# SUperUnioc_analog_ServosExtension.net
KiCad netlist of a schematic drawn in EAGLE
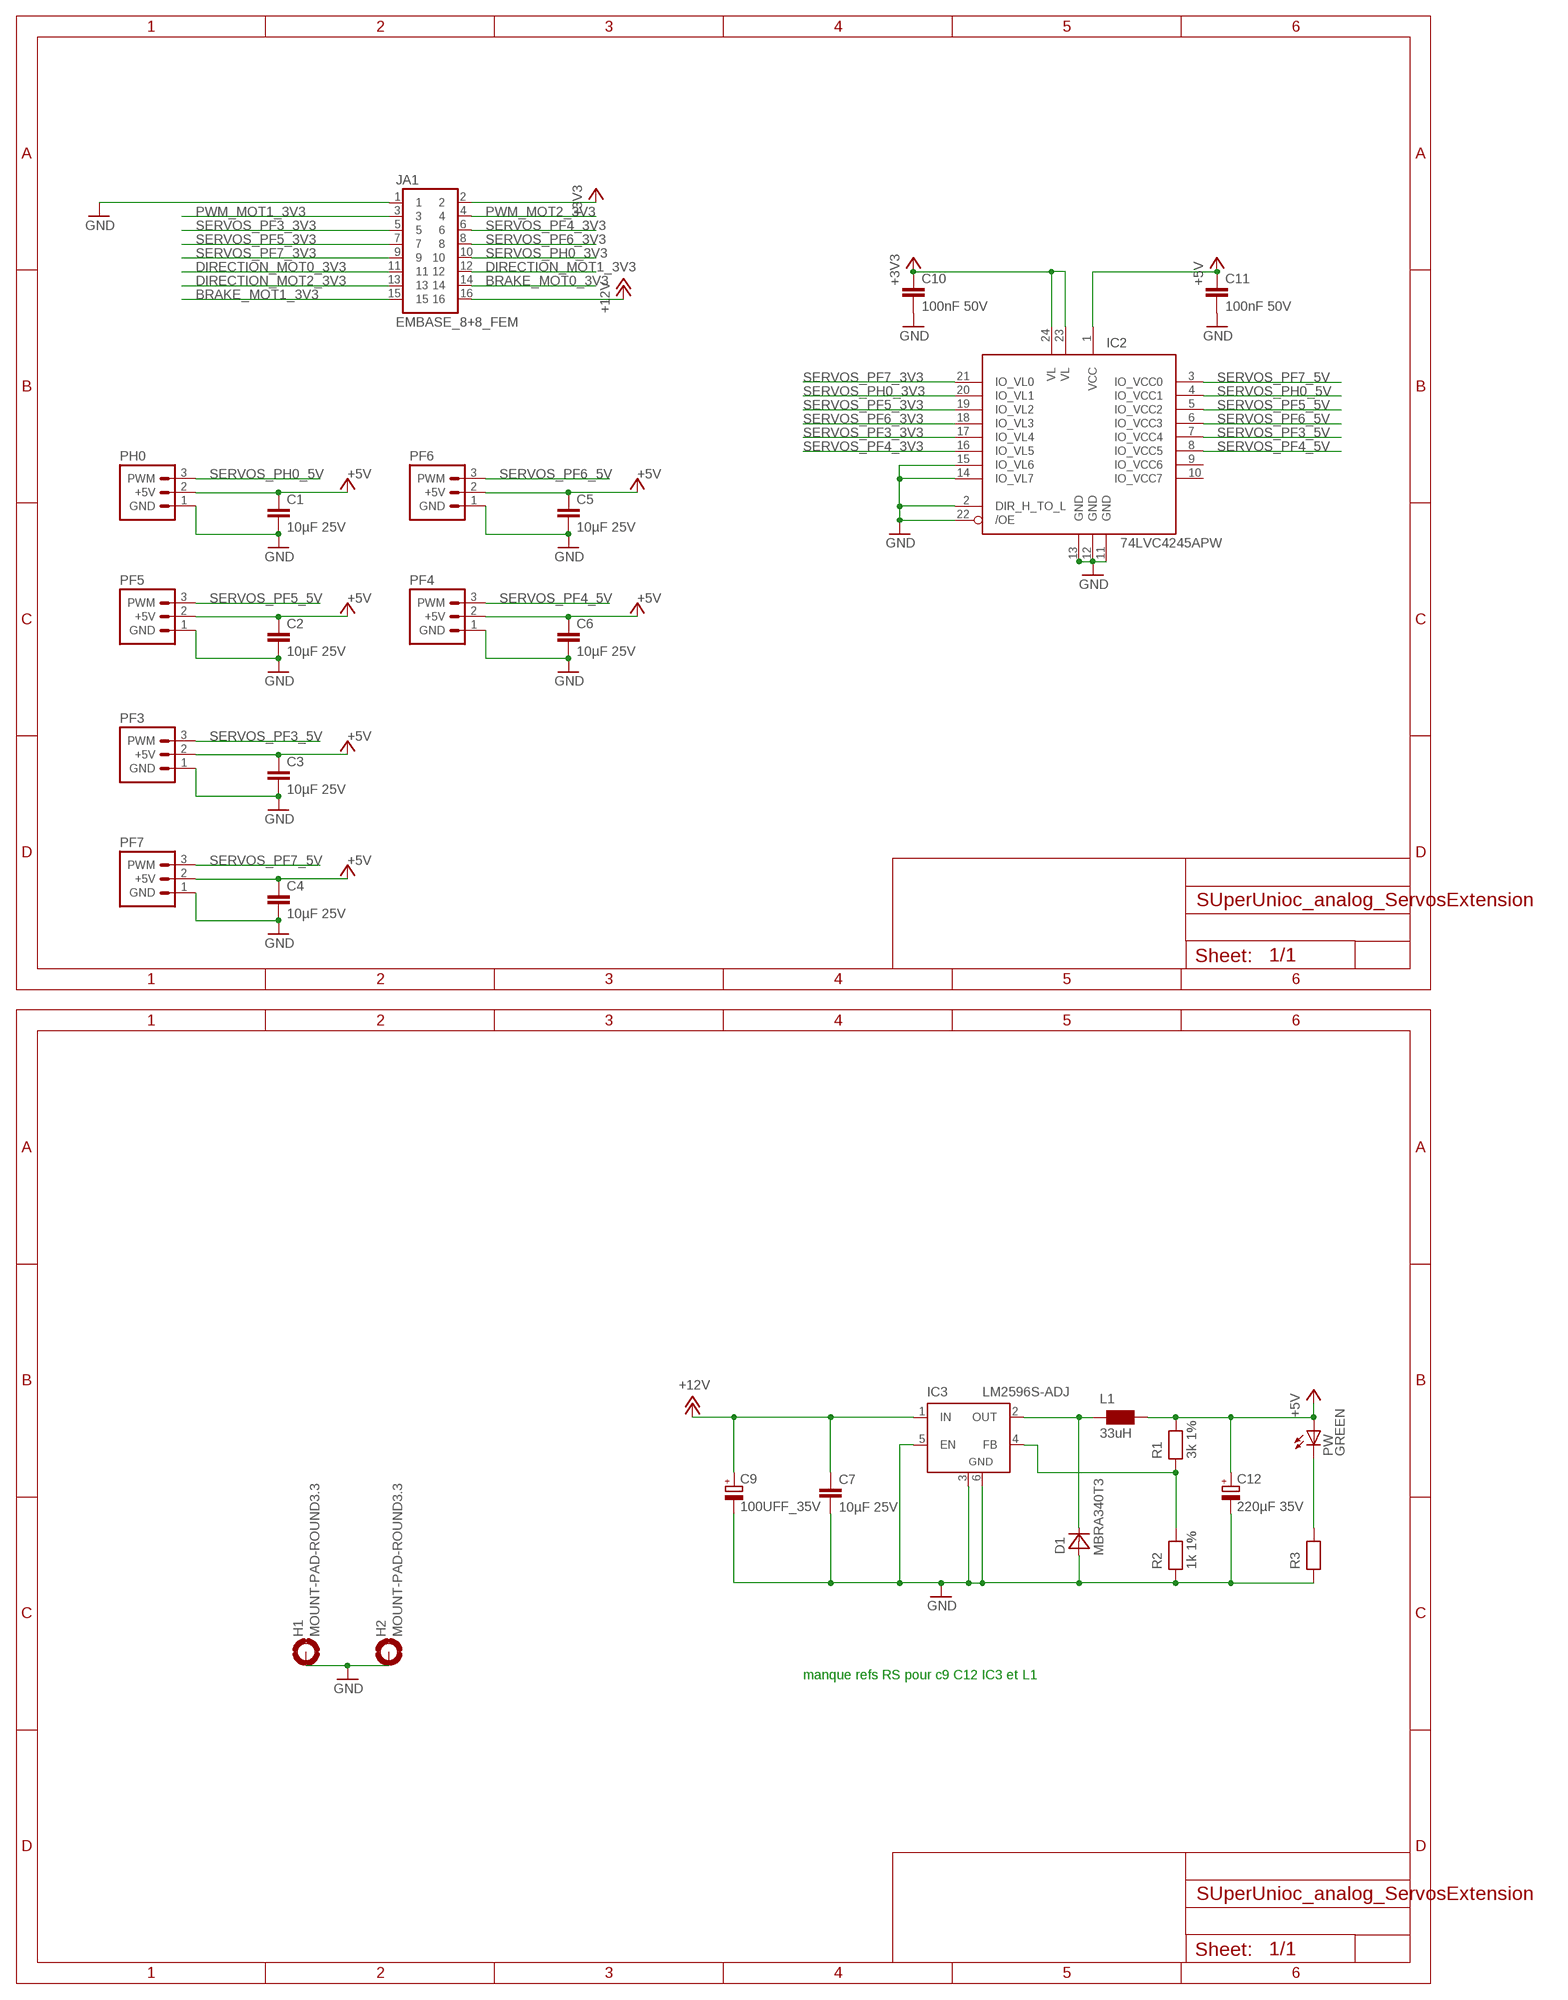
[diagram p0: schematic, sheet 1]

(export (version "E")
  (design (tool "Eeschema 10.0.6"))
  (components
    (comp (ref "C1")
      (value "10µF 25V")
      (footprint "eagle-import:C1210")
      (libsource (lib "eagle-import") (part "10UF-C_25V"))
    )
    (comp (ref "C2")
      (value "10µF 25V")
      (footprint "eagle-import:C1210")
      (libsource (lib "eagle-import") (part "10UF-C_25V"))
    )
    (comp (ref "C3")
      (value "10µF 25V")
      (footprint "eagle-import:C1210")
      (libsource (lib "eagle-import") (part "10UF-C_25V"))
    )
    (comp (ref "C4")
      (value "10µF 25V")
      (footprint "eagle-import:C1210")
      (libsource (lib "eagle-import") (part "10UF-C_25V"))
    )
    (comp (ref "C5")
      (value "10µF 25V")
      (footprint "eagle-import:C1210")
      (libsource (lib "eagle-import") (part "10UF-C_25V"))
    )
    (comp (ref "C6")
      (value "10µF 25V")
      (footprint "eagle-import:C1210")
      (libsource (lib "eagle-import") (part "10UF-C_25V"))
    )
    (comp (ref "C7")
      (value "10µF 25V")
      (footprint "eagle-import:C1210")
      (libsource (lib "eagle-import") (part "10UF-C_25V"))
    )
    (comp (ref "C9")
      (value "100UFF_35V")
      (footprint "eagle-import:PANASONIC_F")
      (libsource (lib "eagle-import") (part "100UFF_35V"))
    )
    (comp (ref "C10")
      (value "100nF 50V")
      (footprint "eagle-import:C0603")
      (libsource (lib "eagle-import") (part "100NF-F"))
    )
    (comp (ref "C11")
      (value "100nF 50V")
      (footprint "eagle-import:C0603")
      (libsource (lib "eagle-import") (part "100NF-F"))
    )
    (comp (ref "C12")
      (value "220µF 35V")
      (footprint "eagle-import:PANASONIC_F")
      (libsource (lib "eagle-import") (part "220UFF_35V"))
    )
    (comp (ref "D1")
      (value "MBRA340T3")
      (footprint "eagle-import:SMA")
      (libsource (lib "eagle-import") (part "MBRA340T3"))
    )
    (comp (ref "H1")
      (value "MOUNT-PAD-ROUND3.3")
      (footprint "eagle-import:3,3-PAD")
      (libsource (lib "eagle-import") (part "MOUNT-PAD-ROUND3.3"))
    )
    (comp (ref "H2")
      (value "MOUNT-PAD-ROUND3.3")
      (footprint "eagle-import:3,3-PAD")
      (libsource (lib "eagle-import") (part "MOUNT-PAD-ROUND3.3"))
    )
    (comp (ref "IC2")
      (value "74LVC4245APW")
      (footprint "eagle-import:TSSOP24")
      (libsource (lib "eagle-import") (part "74LVC4245APW"))
    )
    (comp (ref "IC3")
      (value "LM2596S-ADJ")
      (footprint "eagle-import:TO263-5")
      (libsource (lib "eagle-import") (part "LM2596S-ADJ"))
    )
    (comp (ref "JA1")
      (value "EMBASE_8+8_FEM")
      (footprint "eagle-import:EMBASE_8+8_FEM")
      (libsource (lib "eagle-import") (part "EMBASE_8+8_FEM"))
    )
    (comp (ref "L1")
      (value "33uH")
      (footprint "eagle-import:SRR1280")
      (libsource (lib "eagle-import") (part "33µH-3.3A"))
    )
    (comp (ref "PF3")
      (value "ANALOG_SERVO")
      (footprint "eagle-import:ANALOG_SERVOS")
      (libsource (lib "eagle-import") (part "ANALOG_SERVO"))
    )
    (comp (ref "PF4")
      (value "ANALOG_SERVO")
      (footprint "eagle-import:ANALOG_SERVOS")
      (libsource (lib "eagle-import") (part "ANALOG_SERVO"))
    )
    (comp (ref "PF5")
      (value "ANALOG_SERVO")
      (footprint "eagle-import:ANALOG_SERVOS")
      (libsource (lib "eagle-import") (part "ANALOG_SERVO"))
    )
    (comp (ref "PF6")
      (value "ANALOG_SERVO")
      (footprint "eagle-import:ANALOG_SERVOS")
      (libsource (lib "eagle-import") (part "ANALOG_SERVO"))
    )
    (comp (ref "PF7")
      (value "ANALOG_SERVO")
      (footprint "eagle-import:ANALOG_SERVOS")
      (libsource (lib "eagle-import") (part "ANALOG_SERVO"))
    )
    (comp (ref "PH0")
      (value "ANALOG_SERVO")
      (footprint "eagle-import:ANALOG_SERVOS")
      (libsource (lib "eagle-import") (part "ANALOG_SERVO"))
    )
    (comp (ref "PW")
      (value "GREEN")
      (footprint "eagle-import:CHIP-LED0805")
      (libsource (lib "eagle-import") (part "LED_G"))
    )
    (comp (ref "R1")
      (value "3k 1%")
      (footprint "eagle-import:R0603")
      (libsource (lib "eagle-import") (part "3K09-F"))
    )
    (comp (ref "R2")
      (value "1k 1%")
      (footprint "eagle-import:R0603")
      (libsource (lib "eagle-import") (part "1K-F"))
    )
    (comp (ref "R3")
      (value "470-F")
      (footprint "eagle-import:R0603")
      (libsource (lib "eagle-import") (part "470-F"))
    )
  )
  (nets
    (net (code "1") (name "+3V3") (class "Default")
      (node (ref "C10") (pin "1") (pinfunction "1_1") (pintype "passive"))
      (node (ref "IC2") (pin "23") (pinfunction "VL_23") (pintype "power_in"))
      (node (ref "IC2") (pin "24") (pinfunction "VL_24") (pintype "power_in"))
      (node (ref "JA1") (pin "2") (pinfunction "2_2") (pintype "passive"))
    )
    (net (code "2") (name "+5V") (class "Default")
      (node (ref "C1") (pin "1") (pinfunction "1_1") (pintype "passive"))
      (node (ref "C11") (pin "1") (pinfunction "1_1") (pintype "passive"))
      (node (ref "C12") (pin "+") (pinfunction "+_+") (pintype "passive"))
      (node (ref "C2") (pin "1") (pinfunction "1_1") (pintype "passive"))
      (node (ref "C3") (pin "1") (pinfunction "1_1") (pintype "passive"))
      (node (ref "C4") (pin "1") (pinfunction "1_1") (pintype "passive"))
      (node (ref "C5") (pin "1") (pinfunction "1_1") (pintype "passive"))
      (node (ref "C6") (pin "1") (pinfunction "1_1") (pintype "passive"))
      (node (ref "IC2") (pin "1") (pinfunction "VCC_1") (pintype "power_in"))
      (node (ref "L1") (pin "2") (pinfunction "2_2") (pintype "passive"))
      (node (ref "PF3") (pin "2") (pinfunction "+5V_2") (pintype "passive"))
      (node (ref "PF4") (pin "2") (pinfunction "+5V_2") (pintype "passive"))
      (node (ref "PF5") (pin "2") (pinfunction "+5V_2") (pintype "passive"))
      (node (ref "PF6") (pin "2") (pinfunction "+5V_2") (pintype "passive"))
      (node (ref "PF7") (pin "2") (pinfunction "+5V_2") (pintype "passive"))
      (node (ref "PH0") (pin "2") (pinfunction "+5V_2") (pintype "passive"))
      (node (ref "PW") (pin "A") (pinfunction "A_A") (pintype "passive"))
      (node (ref "R1") (pin "2") (pinfunction "2_2") (pintype "bidirectional"))
    )
    (net (code "3") (name "+12V") (class "Default")
      (node (ref "C7") (pin "1") (pinfunction "1_1") (pintype "passive"))
      (node (ref "C9") (pin "+") (pinfunction "+_+") (pintype "passive"))
      (node (ref "IC3") (pin "1") (pinfunction "IN_1") (pintype "input"))
      (node (ref "JA1") (pin "16") (pinfunction "16_16") (pintype "passive"))
    )
    (net (code "4") (name "/BRAKE_MOT0_3V3") (class "Default")
      (node (ref "JA1") (pin "14") (pinfunction "14_14") (pintype "passive"))
    )
    (net (code "5") (name "/BRAKE_MOT1_3V3") (class "Default")
      (node (ref "JA1") (pin "15") (pinfunction "15_15") (pintype "passive"))
    )
    (net (code "6") (name "/DIRECTION_MOT0_3V3") (class "Default")
      (node (ref "JA1") (pin "11") (pinfunction "11_11") (pintype "passive"))
    )
    (net (code "7") (name "/DIRECTION_MOT1_3V3") (class "Default")
      (node (ref "JA1") (pin "12") (pinfunction "12_12") (pintype "passive"))
    )
    (net (code "8") (name "/DIRECTION_MOT2_3V3") (class "Default")
      (node (ref "JA1") (pin "13") (pinfunction "13_13") (pintype "passive"))
    )
    (net (code "9") (name "/PWM_MOT1_3V3") (class "Default")
      (node (ref "JA1") (pin "3") (pinfunction "3_3") (pintype "passive"))
    )
    (net (code "10") (name "/PWM_MOT2_3V3") (class "Default")
      (node (ref "JA1") (pin "4") (pinfunction "4_4") (pintype "passive"))
    )
    (net (code "11") (name "/SERVOS_PF3_3V3") (class "Default")
      (node (ref "IC2") (pin "17") (pinfunction "IO_VL4_17") (pintype "bidirectional"))
      (node (ref "JA1") (pin "5") (pinfunction "5_5") (pintype "passive"))
    )
    (net (code "12") (name "/SERVOS_PF3_5V") (class "Default")
      (node (ref "IC2") (pin "7") (pinfunction "IO_VCC4_7") (pintype "bidirectional"))
      (node (ref "PF3") (pin "3") (pinfunction "PWM_3") (pintype "passive"))
    )
    (net (code "13") (name "/SERVOS_PF4_3V3") (class "Default")
      (node (ref "IC2") (pin "16") (pinfunction "IO_VL5_16") (pintype "bidirectional"))
      (node (ref "JA1") (pin "6") (pinfunction "6_6") (pintype "passive"))
    )
    (net (code "14") (name "/SERVOS_PF4_5V") (class "Default")
      (node (ref "IC2") (pin "8") (pinfunction "IO_VCC5_8") (pintype "bidirectional"))
      (node (ref "PF4") (pin "3") (pinfunction "PWM_3") (pintype "passive"))
    )
    (net (code "15") (name "/SERVOS_PF5_3V3") (class "Default")
      (node (ref "IC2") (pin "19") (pinfunction "IO_VL2_19") (pintype "bidirectional"))
      (node (ref "JA1") (pin "7") (pinfunction "7_7") (pintype "passive"))
    )
    (net (code "16") (name "/SERVOS_PF5_5V") (class "Default")
      (node (ref "IC2") (pin "5") (pinfunction "IO_VCC2_5") (pintype "bidirectional"))
      (node (ref "PF5") (pin "3") (pinfunction "PWM_3") (pintype "passive"))
    )
    (net (code "17") (name "/SERVOS_PF6_3V3") (class "Default")
      (node (ref "IC2") (pin "18") (pinfunction "IO_VL3_18") (pintype "bidirectional"))
      (node (ref "JA1") (pin "8") (pinfunction "8_8") (pintype "passive"))
    )
    (net (code "18") (name "/SERVOS_PF6_5V") (class "Default")
      (node (ref "IC2") (pin "6") (pinfunction "IO_VCC3_6") (pintype "bidirectional"))
      (node (ref "PF6") (pin "3") (pinfunction "PWM_3") (pintype "passive"))
    )
    (net (code "19") (name "/SERVOS_PF7_3V3") (class "Default")
      (node (ref "IC2") (pin "21") (pinfunction "IO_VL0_21") (pintype "bidirectional"))
      (node (ref "JA1") (pin "9") (pinfunction "9_9") (pintype "passive"))
    )
    (net (code "20") (name "/SERVOS_PF7_5V") (class "Default")
      (node (ref "IC2") (pin "3") (pinfunction "IO_VCC0_3") (pintype "bidirectional"))
      (node (ref "PF7") (pin "3") (pinfunction "PWM_3") (pintype "passive"))
    )
    (net (code "21") (name "/SERVOS_PH0_3V3") (class "Default")
      (node (ref "IC2") (pin "20") (pinfunction "IO_VL1_20") (pintype "bidirectional"))
      (node (ref "JA1") (pin "10") (pinfunction "10_10") (pintype "passive"))
    )
    (net (code "22") (name "/SERVOS_PH0_5V") (class "Default")
      (node (ref "IC2") (pin "4") (pinfunction "IO_VCC1_4") (pintype "bidirectional"))
      (node (ref "PH0") (pin "3") (pinfunction "PWM_3") (pintype "passive"))
    )
    (net (code "23") (name "GND") (class "Default")
      (node (ref "C1") (pin "2") (pinfunction "2_2") (pintype "passive"))
      (node (ref "C10") (pin "2") (pinfunction "2_2") (pintype "passive"))
      (node (ref "C11") (pin "2") (pinfunction "2_2") (pintype "passive"))
      (node (ref "C12") (pin "-") (pinfunction "-_-") (pintype "passive"))
      (node (ref "C2") (pin "2") (pinfunction "2_2") (pintype "passive"))
      (node (ref "C3") (pin "2") (pinfunction "2_2") (pintype "passive"))
      (node (ref "C4") (pin "2") (pinfunction "2_2") (pintype "passive"))
      (node (ref "C5") (pin "2") (pinfunction "2_2") (pintype "passive"))
      (node (ref "C6") (pin "2") (pinfunction "2_2") (pintype "passive"))
      (node (ref "C7") (pin "2") (pinfunction "2_2") (pintype "passive"))
      (node (ref "C9") (pin "-") (pinfunction "-_-") (pintype "passive"))
      (node (ref "D1") (pin "A") (pinfunction "A_A") (pintype "passive"))
      (node (ref "H1") (pin "B3,3") (pinfunction "MOUNT_B3,3") (pintype "passive"))
      (node (ref "H2") (pin "B3,3") (pinfunction "MOUNT_B3,3") (pintype "passive"))
      (node (ref "IC2") (pin "11") (pinfunction "GND_11") (pintype "power_in"))
      (node (ref "IC2") (pin "12") (pinfunction "GND_12") (pintype "power_in"))
      (node (ref "IC2") (pin "13") (pinfunction "GND_13") (pintype "power_in"))
      (node (ref "IC2") (pin "14") (pinfunction "IO_VL7_14") (pintype "bidirectional"))
      (node (ref "IC2") (pin "15") (pinfunction "IO_VL6_15") (pintype "bidirectional"))
      (node (ref "IC2") (pin "2") (pinfunction "DIR_H_TO_L_2") (pintype "bidirectional"))
      (node (ref "IC2") (pin "22") (pinfunction "/OE_22") (pintype "bidirectional"))
      (node (ref "IC3") (pin "3") (pinfunction "GND_3") (pintype "power_in"))
      (node (ref "IC3") (pin "5") (pinfunction "EN_5") (pintype "input"))
      (node (ref "IC3") (pin "6") (pinfunction "GND_6") (pintype "power_in"))
      (node (ref "JA1") (pin "1") (pinfunction "1_1") (pintype "passive"))
      (node (ref "PF3") (pin "1") (pinfunction "GND_1") (pintype "passive"))
      (node (ref "PF4") (pin "1") (pinfunction "GND_1") (pintype "passive"))
      (node (ref "PF5") (pin "1") (pinfunction "GND_1") (pintype "passive"))
      (node (ref "PF6") (pin "1") (pinfunction "GND_1") (pintype "passive"))
      (node (ref "PF7") (pin "1") (pinfunction "GND_1") (pintype "passive"))
      (node (ref "PH0") (pin "1") (pinfunction "GND_1") (pintype "passive"))
      (node (ref "R2") (pin "1") (pinfunction "1_1") (pintype "bidirectional"))
      (node (ref "R3") (pin "1") (pinfunction "1_1") (pintype "bidirectional"))
    )
    (net (code "24") (name "Net-(IC3-FB)") (class "Default")
      (node (ref "IC3") (pin "4") (pinfunction "FB_4") (pintype "input"))
      (node (ref "R1") (pin "1") (pinfunction "1_1") (pintype "bidirectional"))
      (node (ref "R2") (pin "2") (pinfunction "2_2") (pintype "bidirectional"))
    )
    (net (code "25") (name "Net-(IC3-OUT)") (class "Default")
      (node (ref "D1") (pin "C") (pinfunction "C_C") (pintype "passive"))
      (node (ref "IC3") (pin "2") (pinfunction "OUT_2") (pintype "output"))
      (node (ref "L1") (pin "1") (pinfunction "1_1") (pintype "passive"))
    )
    (net (code "26") (name "Net-(PW-PadC)") (class "Default")
      (node (ref "PW") (pin "C") (pinfunction "C_C") (pintype "passive"))
      (node (ref "R3") (pin "2") (pinfunction "2_2") (pintype "bidirectional"))
    )
    (net (code "27") (name "unconnected-(IC2-IO_VCC6-Pad9)") (class "Default")
      (node (ref "IC2") (pin "9") (pinfunction "IO_VCC6_9") (pintype "bidirectional"))
    )
    (net (code "28") (name "unconnected-(IC2-IO_VCC7-Pad10)") (class "Default")
      (node (ref "IC2") (pin "10") (pinfunction "IO_VCC7_10") (pintype "bidirectional"))
    )
  )
)
